# PCB_PROJECT_01.net
KiCad netlist of a schematic drawn in Altium Designer
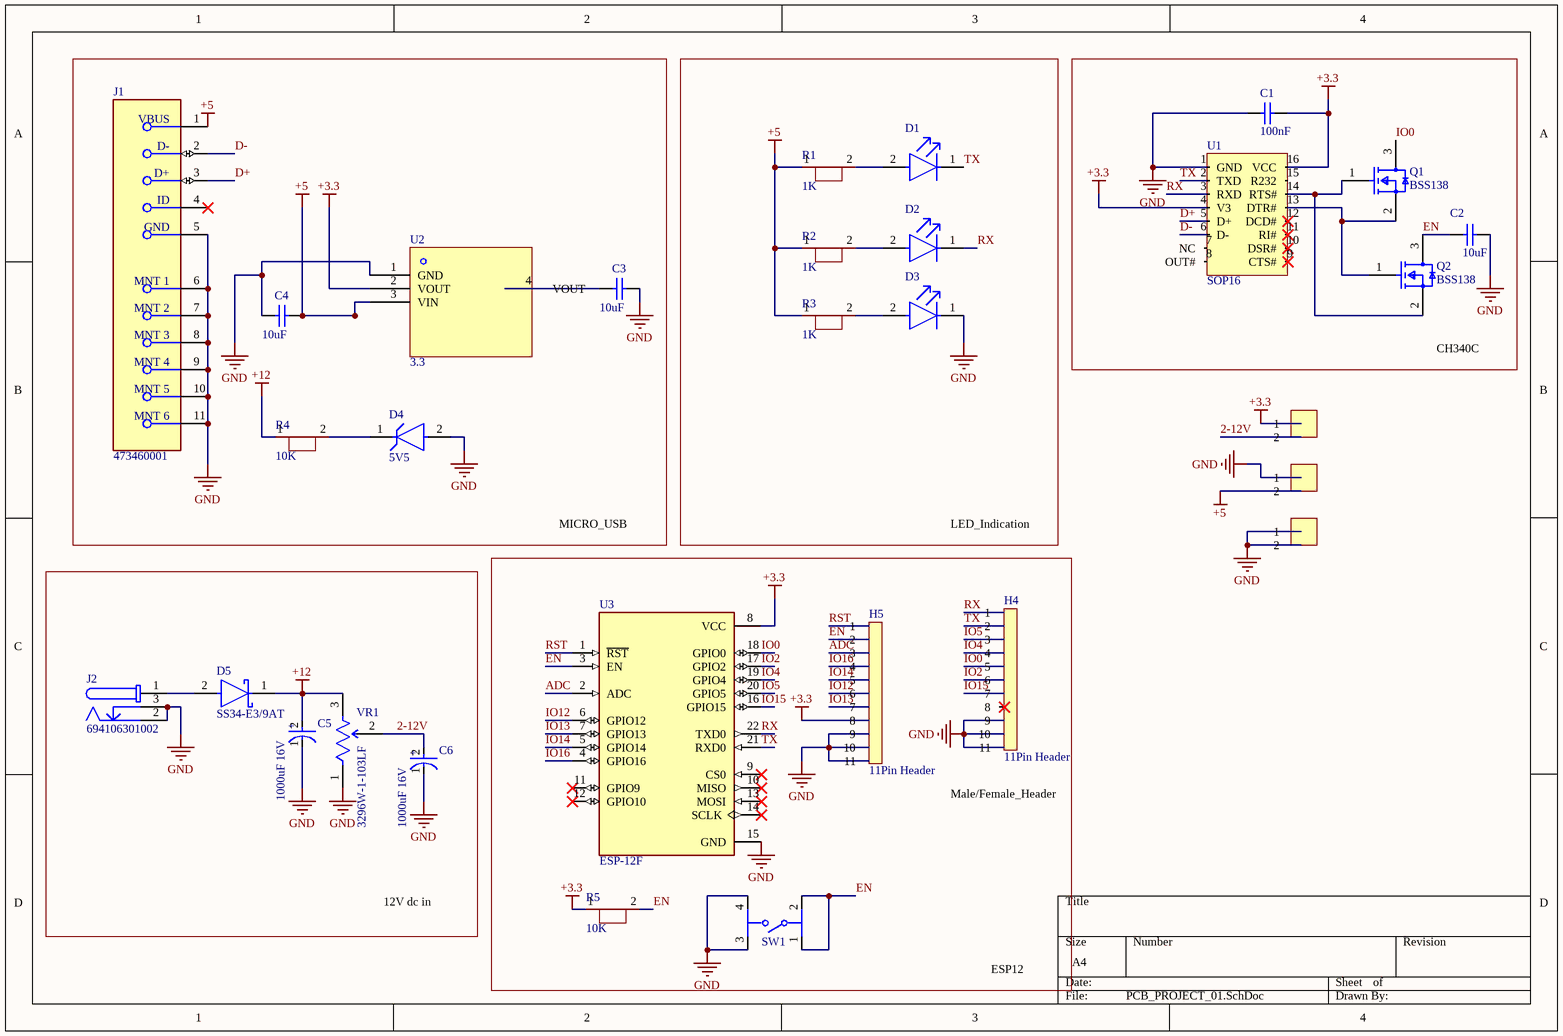
[diagram p0: PCB_PROJECT_01.SchDoc]

(export (version "E")
  (design (tool "Eeschema 10.0.6"))
  (components
    (comp (ref "C1")
      (value "100nF")
      (footprint "CAPC0805(2012)145_M")
      (description "CAP 100nF 100V ±10% 0805 (2012 Metric) Thickness 1.45mm SMD")
      (fields (field (name "TOLERANCE") "Â±10%"))
      (libsource (lib "Altium Content Vault") (part "CAP"))
    )
    (comp (ref "C2")
      (value "10uF")
      (footprint "CAPC0805(2012)145_M")
      (description "CAP 100nF 100V ±10% 0805 (2012 Metric) Thickness 1.45mm SMD")
      (fields (field (name "TOLERANCE") "Â±10%"))
      (libsource (lib "Altium Content Vault") (part "CAP"))
    )
    (comp (ref "C3")
      (value "10uF")
      (footprint "CAPC0805(2012)100_L")
      (fields (field (name "TOLERANCE") "Â±5%"))
      (libsource (lib "Altium Content Vault") (part "CAP"))
    )
    (comp (ref "C4")
      (value "10uF")
      (footprint "CAPC0805(2012)100_L")
      (fields (field (name "TOLERANCE") "Â±5%"))
      (libsource (lib "Altium Content Vault") (part "CAP"))
    )
    (comp (ref "C5")
      (value "1000uF 16V")
      (footprint "FP-RAD-TH-D_10_0_5-L_16_1-MFG")
      (description "Aluminum Electrolytic Capacitors (Radial Lead Type) AEC-Q200 Qualified 1000uF ±20% 16V")
      (fields (field (name "VOLTAGE") "16V") (field (name "TOLERANCE") "20%"))
      (libsource (lib "Altium Content Vault") (part "a00bbbee19879c290e62620ae7e47b1"))
    )
    (comp (ref "C6")
      (value "1000uF 16V")
      (footprint "FP-RAD-TH-D_10_0_5-L_16_1-MFG")
      (description "Aluminum Electrolytic Capacitors (Radial Lead Type) AEC-Q200 Qualified 1000uF ±20% 16V")
      (fields (field (name "VOLTAGE") "16V") (field (name "TOLERANCE") "20%"))
      (libsource (lib "Altium Content Vault") (part "a00bbbee19879c290e62620ae7e47b1"))
    )
    (comp (ref "D1")
      (value "~")
      (footprint "FP-SML-LX0603SIW-TR-MFG")
      (description "LED RED DIFFUSED SMD")
      (libsource (lib "Altium Content Vault") (part "8706943c75ba83719d021d2fdc84c58"))
    )
    (comp (ref "D2")
      (value "SML-LX0603SIW-TR")
      (footprint "FP-SML-LX0603SIW-TR-MFG")
      (description "LED RED DIFFUSED SMD")
      (libsource (lib "Altium Content Vault") (part "8706943c75ba83719d021d2fdc84c58"))
    )
    (comp (ref "D3")
      (value "SML-LX0603SIW-TR")
      (footprint "FP-SML-LX0603SIW-TR-MFG")
      (description "LED RED DIFFUSED SMD")
      (libsource (lib "Altium Content Vault") (part "8706943c75ba83719d021d2fdc84c58"))
    )
    (comp (ref "D4")
      (value "5V5")
      (footprint "FP-SOD123-MFG")
      (description "DIODE ZENER 5.1V 500MW SOD123")
      (fields
        (field (name "MANUFACTURER PART NUMBER") "BZT52C5V1-7-F")
        (field (name "OCTOPART") "https://octopart.com/bzt52c5v1-7-f-diodes+inc.-326718")
      )
      (libsource (lib "Altium Content Vault") (part "f813f71cba58e380607f5dd3caf9714"))
    )
    (comp (ref "D5")
      (value "SS34-E3/9AT")
      (footprint "FP-SMC-MFG")
      (description "DIODE SCHOTTKY 40V 3A DO214AB")
      (libsource (lib "Altium Content Vault") (part "c1678fac7984e62e0809fbf79c06691"))
    )
    (comp (ref "H1")
      (value "HDR_2PIN")
      (footprint "HDR_2PIN")
      (description "2-Pin Header")
      (libsource (lib "C_LIB_ESP") (part "HDR_2PIN"))
    )
    (comp (ref "H2")
      (value "HDR_2PIN")
      (footprint "HDR_2PIN")
      (description "2-Pin Header")
      (libsource (lib "C_LIB_ESP") (part "HDR_2PIN"))
    )
    (comp (ref "H3")
      (value "HDR_2PIN")
      (footprint "HDR_2PIN")
      (description "2-Pin Header")
      (libsource (lib "C_LIB_ESP") (part "HDR_2PIN"))
    )
    (comp (ref "H4")
      (value "11Pin Header")
      (footprint "HDR_11PIN")
      (libsource (lib "C_LIB_ESP") (part "11Pin Header"))
    )
    (comp (ref "H5")
      (value "11Pin Header")
      (footprint "HDR_11PIN")
      (libsource (lib "C_LIB_ESP") (part "11Pin Header"))
    )
    (comp (ref "J1")
      (value "473460001")
      (footprint "FP-473460001-MFG")
      (description "CONN RCPT USB2.0 MICRO B SMD R/A")
      (fields
        (field (name "OCTOPART") "https://octopart.com/47346-0001-molex-7164928")
        (field (name "MANUFACTURER") "Molex")
      )
      (libsource (lib "Altium Content Vault") (part "53ae1f1d9b557310b43ca686e5bb76a"))
    )
    (comp (ref "J2")
      (value "694106301002")
      (footprint "694106301002")
      (description "DC Power Jack Connector WR-DC, Male, Right Angled, THT, 5 A, 24 V")
      (libsource (lib "Altium Content Vault") (part "DC Power Jack"))
    )
    (comp (ref "Q1")
      (value "BSS138")
      (footprint "FP-318-08-IPC_B")
      (description "MOSFET N-CH 50V 220MA SOT-23")
      (libsource (lib "Altium Content Vault") (part "3b9c635fedb024a5347a57b145af9cc"))
    )
    (comp (ref "Q2")
      (value "BSS138")
      (footprint "FP-318-08-IPC_B")
      (description "MOSFET N-CH 50V 220MA SOT-23")
      (libsource (lib "Altium Content Vault") (part "3b9c635fedb024a5347a57b145af9cc"))
    )
    (comp (ref "R1") (value "1K") (footprint "RES0805") (libsource (lib "C_LIB_ESP") (part "RES0805")))
    (comp (ref "R2") (value "1K") (footprint "RES0805") (libsource (lib "C_LIB_ESP") (part "RES0805")))
    (comp (ref "R3") (value "1K") (footprint "RES0805") (libsource (lib "C_LIB_ESP") (part "RES0805")))
    (comp (ref "R4") (value "10K") (footprint "RES0805") (libsource (lib "C_LIB_ESP") (part "RES0805")))
    (comp (ref "R5") (value "10K") (footprint "RES0805") (libsource (lib "C_LIB_ESP") (part "RES0805")))
    (comp (ref "SW1")
      (value "B3F-1055")
      (footprint "FP-B3F-1055-MFG")
      (description "SWITCH TACTILE SPST-NO 0.05A 24V")
      (libsource (lib "Altium Content Vault") (part "b8895f3f4cefb76e1819d2863dba89b"))
    )
    (comp (ref "U1") (value "SOP16") (footprint "CH340C") (libsource (lib "C_LIB_ESP") (part "CH3400C")))
    (comp (ref "U2")
      (value "3.3")
      (footprint "AMS11173.3")
      (description "3LEAD SOT-223 PLASTIC PACKAGE")
      (libsource (lib "C_LIB_ESP") (part "AMS11173.3"))
    )
    (comp (ref "U3")
      (value "ESP-12F")
      (footprint "XCVR_ESP-12F")
      (description "WiFi Module")
      (fields (field (name "MF") "AI-Thinker"))
      (libsource (lib "ESP-12F") (part "ESP-12F"))
    )
    (comp (ref "VR1")
      (value "3296W-1-103LF")
      (footprint "FP-3296W-MFG")
      (description "TRIMMER 10K OHM 0.5W PC PIN TOP")
      (fields (field (name "TOLERANCE") "10%"))
      (libsource (lib "Altium Content Vault") (part "2dcfd2547301a7d3209a5e99acfd772"))
    )
  )
  (nets
    (net (code "1") (name "+3.3") (class "Default")
      (node (ref "C1") (pin "2") (pinfunction "2_2") (pintype "passive"))
      (node (ref "H1") (pin "1") (pinfunction "1_1") (pintype "passive"))
      (node (ref "H5") (pin "8") (pinfunction "8_8") (pintype "passive"))
      (node (ref "R5") (pin "1") (pinfunction "0_1") (pintype "passive"))
      (node (ref "U1") (pin "16") (pinfunction "VCC_16") (pintype "power_in"))
      (node (ref "U1") (pin "4") (pinfunction "V3_4") (pintype "power_in"))
      (node (ref "U2") (pin "2") (pinfunction "VOUT_2") (pintype "passive"))
      (node (ref "U3") (pin "8") (pinfunction "VCC_8") (pintype "power_in"))
    )
    (net (code "2") (name "+5") (class "Default")
      (node (ref "C4") (pin "2") (pinfunction "2_2") (pintype "passive"))
      (node (ref "H2") (pin "2") (pinfunction "2_2") (pintype "passive"))
      (node (ref "J1") (pin "1") (pinfunction "VBUS_1") (pintype "power_in"))
      (node (ref "R1") (pin "1") (pinfunction "0_1") (pintype "passive"))
      (node (ref "R2") (pin "1") (pinfunction "0_1") (pintype "passive"))
      (node (ref "R3") (pin "1") (pinfunction "0_1") (pintype "passive"))
      (node (ref "U2") (pin "3") (pinfunction "VIN_3") (pintype "passive"))
    )
    (net (code "3") (name "+12") (class "Default")
      (node (ref "C5") (pin "2") (pinfunction "A_2") (pintype "passive"))
      (node (ref "D5") (pin "1") (pinfunction "C_1") (pintype "passive"))
      (node (ref "R4") (pin "1") (pinfunction "0_1") (pintype "passive"))
      (node (ref "VR1") (pin "3") (pinfunction "CW_3") (pintype "passive"))
    )
    (net (code "4") (name "/2-12V") (class "Default")
      (node (ref "C6") (pin "2") (pinfunction "A_2") (pintype "passive"))
      (node (ref "H1") (pin "2") (pinfunction "2_2") (pintype "passive"))
      (node (ref "VR1") (pin "2") (pinfunction "WIPER_2") (pintype "passive"))
    )
    (net (code "5") (name "/ADC") (class "Default")
      (node (ref "H5") (pin "3") (pinfunction "3_3") (pintype "passive"))
      (node (ref "U3") (pin "2") (pinfunction "ADC_2") (pintype "input"))
    )
    (net (code "6") (name "/D+") (class "Default")
      (node (ref "J1") (pin "3") (pinfunction "D+_3") (pintype "bidirectional"))
      (node (ref "U1") (pin "5") (pinfunction "D+_5") (pintype "passive"))
    )
    (net (code "7") (name "/D-") (class "Default")
      (node (ref "J1") (pin "2") (pinfunction "D-_2") (pintype "bidirectional"))
      (node (ref "U1") (pin "6") (pinfunction "D-_6") (pintype "passive"))
    )
    (net (code "8") (name "/EN") (class "Default")
      (node (ref "C2") (pin "1") (pinfunction "1_1") (pintype "passive"))
      (node (ref "H5") (pin "2") (pinfunction "2_2") (pintype "passive"))
      (node (ref "Q2") (pin "3") (pinfunction "D_3") (pintype "passive"))
      (node (ref "R5") (pin "2") (pinfunction "2_2") (pintype "passive"))
      (node (ref "SW1") (pin "1") (pinfunction "1_1") (pintype "passive"))
      (node (ref "SW1") (pin "2") (pinfunction "2_2") (pintype "passive"))
      (node (ref "U3") (pin "3") (pinfunction "EN_3") (pintype "input"))
    )
    (net (code "9") (name "/IO0") (class "Default")
      (node (ref "H4") (pin "5") (pinfunction "5_5") (pintype "passive"))
      (node (ref "Q1") (pin "3") (pinfunction "D_3") (pintype "passive"))
      (node (ref "U3") (pin "18") (pinfunction "GPIO0_18") (pintype "bidirectional"))
    )
    (net (code "10") (name "/IO2") (class "Default")
      (node (ref "H4") (pin "6") (pinfunction "6_6") (pintype "passive"))
      (node (ref "U3") (pin "17") (pinfunction "GPIO2_17") (pintype "bidirectional"))
    )
    (net (code "11") (name "/IO4") (class "Default")
      (node (ref "H4") (pin "4") (pinfunction "4_4") (pintype "passive"))
      (node (ref "U3") (pin "19") (pinfunction "GPIO4_19") (pintype "bidirectional"))
    )
    (net (code "12") (name "/IO5") (class "Default")
      (node (ref "H4") (pin "3") (pinfunction "3_3") (pintype "passive"))
      (node (ref "U3") (pin "20") (pinfunction "GPIO5_20") (pintype "bidirectional"))
    )
    (net (code "13") (name "/IO12") (class "Default")
      (node (ref "H5") (pin "6") (pinfunction "6_6") (pintype "passive"))
      (node (ref "U3") (pin "6") (pinfunction "GPIO12_6") (pintype "bidirectional"))
    )
    (net (code "14") (name "/IO13") (class "Default")
      (node (ref "H5") (pin "7") (pinfunction "7_7") (pintype "passive"))
      (node (ref "U3") (pin "7") (pinfunction "GPIO13_7") (pintype "bidirectional"))
    )
    (net (code "15") (name "/IO14") (class "Default")
      (node (ref "H5") (pin "5") (pinfunction "5_5") (pintype "passive"))
      (node (ref "U3") (pin "5") (pinfunction "GPIO14_5") (pintype "bidirectional"))
    )
    (net (code "16") (name "/IO15") (class "Default")
      (node (ref "H4") (pin "7") (pinfunction "7_7") (pintype "passive"))
      (node (ref "U3") (pin "16") (pinfunction "GPIO15_16") (pintype "bidirectional"))
    )
    (net (code "17") (name "/IO16") (class "Default")
      (node (ref "H5") (pin "4") (pinfunction "4_4") (pintype "passive"))
      (node (ref "U3") (pin "4") (pinfunction "GPIO16_4") (pintype "bidirectional"))
    )
    (net (code "18") (name "/RST") (class "Default")
      (node (ref "H5") (pin "1") (pinfunction "1_1") (pintype "passive"))
      (node (ref "U3") (pin "1") (pinfunction "~{RST}_1") (pintype "input"))
    )
    (net (code "19") (name "/RX") (class "Default")
      (node (ref "D2") (pin "1") (pinfunction "C_1") (pintype "passive"))
      (node (ref "H4") (pin "1") (pinfunction "1_1") (pintype "passive"))
      (node (ref "U1") (pin "3") (pinfunction "RXD_3") (pintype "input"))
      (node (ref "U3") (pin "22") (pinfunction "TXD0_22") (pintype "output"))
    )
    (net (code "20") (name "/TX") (class "Default")
      (node (ref "D1") (pin "1") (pinfunction "C_1") (pintype "passive"))
      (node (ref "H4") (pin "2") (pinfunction "2_2") (pintype "passive"))
      (node (ref "U1") (pin "2") (pinfunction "TXD_2") (pintype "output"))
      (node (ref "U3") (pin "21") (pinfunction "RXD0_21") (pintype "input"))
    )
    (net (code "21") (name "GND") (class "Default")
      (node (ref "C1") (pin "1") (pinfunction "1_1") (pintype "passive"))
      (node (ref "C2") (pin "2") (pinfunction "2_2") (pintype "passive"))
      (node (ref "C3") (pin "2") (pinfunction "2_2") (pintype "passive"))
      (node (ref "C4") (pin "1") (pinfunction "1_1") (pintype "passive"))
      (node (ref "C5") (pin "1") (pinfunction "C_1") (pintype "passive"))
      (node (ref "C6") (pin "1") (pinfunction "C_1") (pintype "passive"))
      (node (ref "D3") (pin "1") (pinfunction "C_1") (pintype "passive"))
      (node (ref "D4") (pin "2") (pinfunction "A_2") (pintype "passive"))
      (node (ref "H2") (pin "1") (pinfunction "1_1") (pintype "passive"))
      (node (ref "H3") (pin "1") (pinfunction "1_1") (pintype "passive"))
      (node (ref "H3") (pin "2") (pinfunction "2_2") (pintype "passive"))
      (node (ref "H4") (pin "10") (pinfunction "10_10") (pintype "passive"))
      (node (ref "H4") (pin "11") (pinfunction "11_11") (pintype "passive"))
      (node (ref "H4") (pin "9") (pinfunction "9_9") (pintype "passive"))
      (node (ref "H5") (pin "10") (pinfunction "10_10") (pintype "passive"))
      (node (ref "H5") (pin "11") (pinfunction "11_11") (pintype "passive"))
      (node (ref "H5") (pin "9") (pinfunction "9_9") (pintype "passive"))
      (node (ref "J1") (pin "10") (pinfunction "MNT_5_10") (pintype "passive"))
      (node (ref "J1") (pin "11") (pinfunction "MNT_6_11") (pintype "passive"))
      (node (ref "J1") (pin "5") (pinfunction "GND_5") (pintype "power_in"))
      (node (ref "J1") (pin "6") (pinfunction "MNT_1_6") (pintype "passive"))
      (node (ref "J1") (pin "7") (pinfunction "MNT_2_7") (pintype "passive"))
      (node (ref "J1") (pin "8") (pinfunction "MNT_3_8") (pintype "passive"))
      (node (ref "J1") (pin "9") (pinfunction "MNT_4_9") (pintype "passive"))
      (node (ref "J2") (pin "2") (pinfunction "2_2") (pintype "passive"))
      (node (ref "J2") (pin "3") (pinfunction "3_3") (pintype "passive"))
      (node (ref "SW1") (pin "3") (pinfunction "3_3") (pintype "passive"))
      (node (ref "SW1") (pin "4") (pinfunction "4_4") (pintype "passive"))
      (node (ref "U1") (pin "1") (pinfunction "GND_1") (pintype "power_in"))
      (node (ref "U2") (pin "1") (pinfunction "GND_1") (pintype "passive"))
      (node (ref "U3") (pin "15") (pinfunction "GND_15") (pintype "power_in"))
      (node (ref "VR1") (pin "1") (pinfunction "CCW_1") (pintype "passive"))
    )
    (net (code "22") (name "Net-(C3-Pad1)") (class "Default")
      (node (ref "C3") (pin "1") (pinfunction "1_1") (pintype "passive"))
      (node (ref "U2") (pin "4") (pinfunction "VOUT_4") (pintype "passive"))
    )
    (net (code "23") (name "Net-(D1-A)") (class "Default")
      (node (ref "D1") (pin "2") (pinfunction "A_2") (pintype "passive"))
      (node (ref "R1") (pin "2") (pinfunction "2_2") (pintype "passive"))
    )
    (net (code "24") (name "Net-(D2-A)") (class "Default")
      (node (ref "D2") (pin "2") (pinfunction "A_2") (pintype "passive"))
      (node (ref "R2") (pin "2") (pinfunction "2_2") (pintype "passive"))
    )
    (net (code "25") (name "Net-(D3-A)") (class "Default")
      (node (ref "D3") (pin "2") (pinfunction "A_2") (pintype "passive"))
      (node (ref "R3") (pin "2") (pinfunction "2_2") (pintype "passive"))
    )
    (net (code "26") (name "Net-(D4-C)") (class "Default")
      (node (ref "D4") (pin "1") (pinfunction "C_1") (pintype "passive"))
      (node (ref "R4") (pin "2") (pinfunction "2_2") (pintype "passive"))
    )
    (net (code "27") (name "Net-(D5-A)") (class "Default")
      (node (ref "D5") (pin "2") (pinfunction "A_2") (pintype "passive"))
      (node (ref "J2") (pin "1") (pinfunction "1_1") (pintype "passive"))
    )
    (net (code "28") (name "Net-(Q1-G)") (class "Default")
      (node (ref "Q1") (pin "1") (pinfunction "G_1") (pintype "passive"))
      (node (ref "Q2") (pin "2") (pinfunction "S_2") (pintype "passive"))
      (node (ref "U1") (pin "14") (pinfunction "RTS#_14") (pintype "output"))
    )
    (net (code "29") (name "Net-(Q1-S)") (class "Default")
      (node (ref "Q1") (pin "2") (pinfunction "S_2") (pintype "passive"))
      (node (ref "Q2") (pin "1") (pinfunction "G_1") (pintype "passive"))
      (node (ref "U1") (pin "13") (pinfunction "DTR#_13") (pintype "output"))
    )
    (net (code "30") (name "unconnected-(H4-Pad8)") (class "Default")
      (node (ref "H4") (pin "8") (pinfunction "8_8") (pintype "passive+no_connect"))
    )
    (net (code "31") (name "unconnected-(J1-ID-Pad4)") (class "Default")
      (node (ref "J1") (pin "4") (pinfunction "ID_4") (pintype "passive+no_connect"))
    )
    (net (code "32") (name "unconnected-(U1-CTS#-Pad9)") (class "Default")
      (node (ref "U1") (pin "9") (pinfunction "CTS#_9") (pintype "input+no_connect"))
    )
    (net (code "33") (name "unconnected-(U1-DCD#-Pad12)") (class "Default")
      (node (ref "U1") (pin "12") (pinfunction "DCD#_12") (pintype "input+no_connect"))
    )
    (net (code "34") (name "unconnected-(U1-DSR#-Pad10)") (class "Default")
      (node (ref "U1") (pin "10") (pinfunction "DSR#_10") (pintype "input+no_connect"))
    )
    (net (code "35") (name "unconnected-(U1-NC-Pad7)") (class "Default")
      (node (ref "U1") (pin "7") (pinfunction "NC_7") (pintype "passive"))
    )
    (net (code "36") (name "unconnected-(U1-OUT#-Pad8)") (class "Default")
      (node (ref "U1") (pin "8") (pinfunction "OUT#_8") (pintype "output"))
    )
    (net (code "37") (name "unconnected-(U1-R232-Pad15)") (class "Default")
      (node (ref "U1") (pin "15") (pinfunction "R232_15") (pintype "passive"))
    )
    (net (code "38") (name "unconnected-(U1-RI#-Pad11)") (class "Default")
      (node (ref "U1") (pin "11") (pinfunction "RI#_11") (pintype "input+no_connect"))
    )
    (net (code "39") (name "unconnected-(U3-CS0-Pad9)") (class "Default")
      (node (ref "U3") (pin "9") (pinfunction "CS0_9") (pintype "input+no_connect"))
    )
    (net (code "40") (name "unconnected-(U3-GPIO9-Pad11)") (class "Default")
      (node (ref "U3") (pin "11") (pinfunction "GPIO9_11") (pintype "bidirectional+no_connect"))
    )
    (net (code "41") (name "unconnected-(U3-GPIO10-Pad12)") (class "Default")
      (node (ref "U3") (pin "12") (pinfunction "GPIO10_12") (pintype "bidirectional+no_connect"))
    )
    (net (code "42") (name "unconnected-(U3-MISO-Pad10)") (class "Default")
      (node (ref "U3") (pin "10") (pinfunction "MISO_10") (pintype "output+no_connect"))
    )
    (net (code "43") (name "unconnected-(U3-MOSI-Pad13)") (class "Default")
      (node (ref "U3") (pin "13") (pinfunction "MOSI_13") (pintype "input+no_connect"))
    )
    (net (code "44") (name "unconnected-(U3-SCLK-Pad14)") (class "Default")
      (node (ref "U3") (pin "14") (pinfunction "SCLK_14") (pintype "output+no_connect"))
    )
  )
)
